# nixie.net
KiCad netlist of a schematic drawn in EAGLE
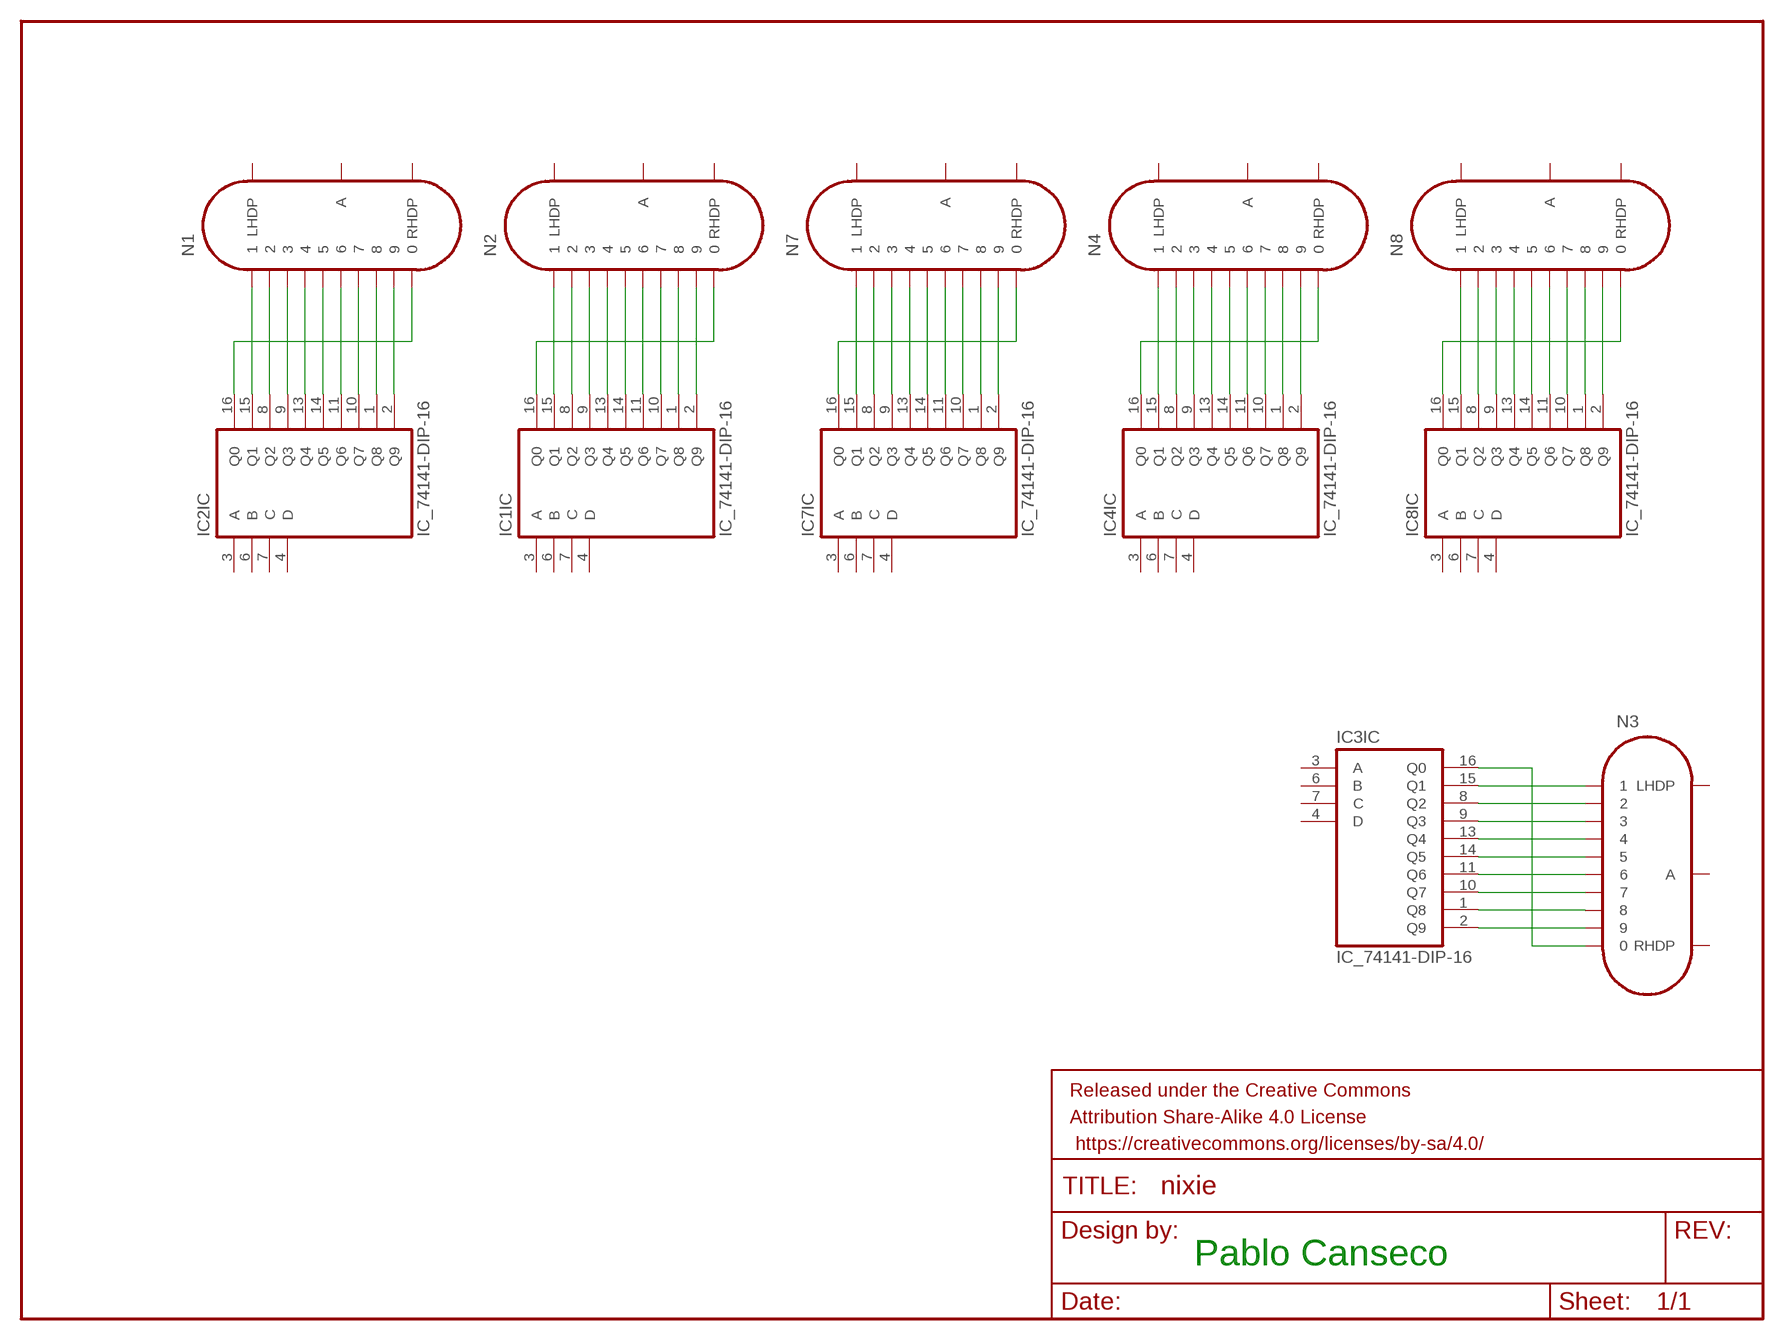
[diagram p0: schematic, sheet 1]

(export (version "E")
  (design (tool "Eeschema 10.0.6"))
  (components
    (comp (ref "FRAME1")
      (value "FRAME-LETTER")
      (footprint "eagle-import:CREATIVE_COMMONS")
      (libsource (lib "eagle-import") (part "FRAME-LETTER"))
    )
    (comp (ref "IC1")
      (value "IC_74141-DIP-16")
      (footprint "eagle-import:DIL16")
      (libsource (lib "eagle-import") (part "IC_74141-DIP-16"))
    )
    (comp (ref "IC2")
      (value "IC_74141-DIP-16")
      (footprint "eagle-import:DIL16")
      (libsource (lib "eagle-import") (part "IC_74141-DIP-16"))
    )
    (comp (ref "IC3")
      (value "IC_74141-DIP-16")
      (footprint "eagle-import:DIL16")
      (libsource (lib "eagle-import") (part "IC_74141-DIP-16"))
    )
    (comp (ref "IC4")
      (value "IC_74141-DIP-16")
      (footprint "eagle-import:DIL16")
      (libsource (lib "eagle-import") (part "IC_74141-DIP-16"))
    )
    (comp (ref "IC7")
      (value "IC_74141-DIP-16")
      (footprint "eagle-import:DIL16")
      (libsource (lib "eagle-import") (part "IC_74141-DIP-16"))
    )
    (comp (ref "IC8")
      (value "IC_74141-DIP-16")
      (footprint "eagle-import:DIL16")
      (libsource (lib "eagle-import") (part "IC_74141-DIP-16"))
    )
    (comp (ref "N1")
      (value "IN-16")
      (footprint "eagle-import:IN-16")
      (libsource (lib "eagle-import") (part "IN-16"))
    )
    (comp (ref "N2")
      (value "IN-16")
      (footprint "eagle-import:IN-16")
      (libsource (lib "eagle-import") (part "IN-16"))
    )
    (comp (ref "N3")
      (value "IN-16")
      (footprint "eagle-import:IN-16")
      (libsource (lib "eagle-import") (part "IN-16"))
    )
    (comp (ref "N4")
      (value "IN-16")
      (footprint "eagle-import:IN-16")
      (libsource (lib "eagle-import") (part "IN-16"))
    )
    (comp (ref "N7")
      (value "IN-16")
      (footprint "eagle-import:IN-16")
      (libsource (lib "eagle-import") (part "IN-16"))
    )
    (comp (ref "N8")
      (value "IN-16")
      (footprint "eagle-import:IN-16")
      (libsource (lib "eagle-import") (part "IN-16"))
    )
  )
  (nets
    (net (code "1") (name "Net-(IC1A-Q0)") (class "Default")
      (node (ref "IC1") (pin "16") (pinfunction "Q0_16") (pintype "output"))
      (node (ref "N2") (pin "0") (pinfunction "0_0") (pintype "bidirectional"))
    )
    (net (code "2") (name "Net-(IC1A-Q1)") (class "Default")
      (node (ref "IC1") (pin "15") (pinfunction "Q1_15") (pintype "output"))
      (node (ref "N2") (pin "1") (pinfunction "1_1") (pintype "bidirectional"))
    )
    (net (code "3") (name "Net-(IC1A-Q2)") (class "Default")
      (node (ref "IC1") (pin "8") (pinfunction "Q2_8") (pintype "output"))
      (node (ref "N2") (pin "2") (pinfunction "2_2") (pintype "bidirectional"))
    )
    (net (code "4") (name "Net-(IC1A-Q3)") (class "Default")
      (node (ref "IC1") (pin "9") (pinfunction "Q3_9") (pintype "output"))
      (node (ref "N2") (pin "3") (pinfunction "3_3") (pintype "bidirectional"))
    )
    (net (code "5") (name "Net-(IC1A-Q4)") (class "Default")
      (node (ref "IC1") (pin "13") (pinfunction "Q4_13") (pintype "output"))
      (node (ref "N2") (pin "4") (pinfunction "4_4") (pintype "bidirectional"))
    )
    (net (code "6") (name "Net-(IC1A-Q5)") (class "Default")
      (node (ref "IC1") (pin "14") (pinfunction "Q5_14") (pintype "output"))
      (node (ref "N2") (pin "5") (pinfunction "5_5") (pintype "bidirectional"))
    )
    (net (code "7") (name "Net-(IC1A-Q6)") (class "Default")
      (node (ref "IC1") (pin "11") (pinfunction "Q6_11") (pintype "output"))
      (node (ref "N2") (pin "6") (pinfunction "6_6") (pintype "bidirectional"))
    )
    (net (code "8") (name "Net-(IC1A-Q7)") (class "Default")
      (node (ref "IC1") (pin "10") (pinfunction "Q7_10") (pintype "output"))
      (node (ref "N2") (pin "7") (pinfunction "7_7") (pintype "bidirectional"))
    )
    (net (code "9") (name "Net-(IC1A-Q8)") (class "Default")
      (node (ref "IC1") (pin "1") (pinfunction "Q8_1") (pintype "output"))
      (node (ref "N2") (pin "8") (pinfunction "8_8") (pintype "bidirectional"))
    )
    (net (code "10") (name "Net-(IC1A-Q9)") (class "Default")
      (node (ref "IC1") (pin "2") (pinfunction "Q9_2") (pintype "output"))
      (node (ref "N2") (pin "9") (pinfunction "9_9") (pintype "bidirectional"))
    )
    (net (code "11") (name "Net-(IC2A-Q0)") (class "Default")
      (node (ref "IC2") (pin "16") (pinfunction "Q0_16") (pintype "output"))
      (node (ref "N1") (pin "0") (pinfunction "0_0") (pintype "bidirectional"))
    )
    (net (code "12") (name "Net-(IC2A-Q1)") (class "Default")
      (node (ref "IC2") (pin "15") (pinfunction "Q1_15") (pintype "output"))
      (node (ref "N1") (pin "1") (pinfunction "1_1") (pintype "bidirectional"))
    )
    (net (code "13") (name "Net-(IC2A-Q2)") (class "Default")
      (node (ref "IC2") (pin "8") (pinfunction "Q2_8") (pintype "output"))
      (node (ref "N1") (pin "2") (pinfunction "2_2") (pintype "bidirectional"))
    )
    (net (code "14") (name "Net-(IC2A-Q3)") (class "Default")
      (node (ref "IC2") (pin "9") (pinfunction "Q3_9") (pintype "output"))
      (node (ref "N1") (pin "3") (pinfunction "3_3") (pintype "bidirectional"))
    )
    (net (code "15") (name "Net-(IC2A-Q4)") (class "Default")
      (node (ref "IC2") (pin "13") (pinfunction "Q4_13") (pintype "output"))
      (node (ref "N1") (pin "4") (pinfunction "4_4") (pintype "bidirectional"))
    )
    (net (code "16") (name "Net-(IC2A-Q5)") (class "Default")
      (node (ref "IC2") (pin "14") (pinfunction "Q5_14") (pintype "output"))
      (node (ref "N1") (pin "5") (pinfunction "5_5") (pintype "bidirectional"))
    )
    (net (code "17") (name "Net-(IC2A-Q6)") (class "Default")
      (node (ref "IC2") (pin "11") (pinfunction "Q6_11") (pintype "output"))
      (node (ref "N1") (pin "6") (pinfunction "6_6") (pintype "bidirectional"))
    )
    (net (code "18") (name "Net-(IC2A-Q7)") (class "Default")
      (node (ref "IC2") (pin "10") (pinfunction "Q7_10") (pintype "output"))
      (node (ref "N1") (pin "7") (pinfunction "7_7") (pintype "bidirectional"))
    )
    (net (code "19") (name "Net-(IC2A-Q8)") (class "Default")
      (node (ref "IC2") (pin "1") (pinfunction "Q8_1") (pintype "output"))
      (node (ref "N1") (pin "8") (pinfunction "8_8") (pintype "bidirectional"))
    )
    (net (code "20") (name "Net-(IC2A-Q9)") (class "Default")
      (node (ref "IC2") (pin "2") (pinfunction "Q9_2") (pintype "output"))
      (node (ref "N1") (pin "9") (pinfunction "9_9") (pintype "bidirectional"))
    )
    (net (code "21") (name "Net-(IC3A-Q0)") (class "Default")
      (node (ref "IC3") (pin "16") (pinfunction "Q0_16") (pintype "output"))
      (node (ref "N3") (pin "0") (pinfunction "0_0") (pintype "bidirectional"))
    )
    (net (code "22") (name "Net-(IC3A-Q1)") (class "Default")
      (node (ref "IC3") (pin "15") (pinfunction "Q1_15") (pintype "output"))
      (node (ref "N3") (pin "1") (pinfunction "1_1") (pintype "bidirectional"))
    )
    (net (code "23") (name "Net-(IC3A-Q2)") (class "Default")
      (node (ref "IC3") (pin "8") (pinfunction "Q2_8") (pintype "output"))
      (node (ref "N3") (pin "2") (pinfunction "2_2") (pintype "bidirectional"))
    )
    (net (code "24") (name "Net-(IC3A-Q3)") (class "Default")
      (node (ref "IC3") (pin "9") (pinfunction "Q3_9") (pintype "output"))
      (node (ref "N3") (pin "3") (pinfunction "3_3") (pintype "bidirectional"))
    )
    (net (code "25") (name "Net-(IC3A-Q4)") (class "Default")
      (node (ref "IC3") (pin "13") (pinfunction "Q4_13") (pintype "output"))
      (node (ref "N3") (pin "4") (pinfunction "4_4") (pintype "bidirectional"))
    )
    (net (code "26") (name "Net-(IC3A-Q5)") (class "Default")
      (node (ref "IC3") (pin "14") (pinfunction "Q5_14") (pintype "output"))
      (node (ref "N3") (pin "5") (pinfunction "5_5") (pintype "bidirectional"))
    )
    (net (code "27") (name "Net-(IC3A-Q6)") (class "Default")
      (node (ref "IC3") (pin "11") (pinfunction "Q6_11") (pintype "output"))
      (node (ref "N3") (pin "6") (pinfunction "6_6") (pintype "bidirectional"))
    )
    (net (code "28") (name "Net-(IC3A-Q7)") (class "Default")
      (node (ref "IC3") (pin "10") (pinfunction "Q7_10") (pintype "output"))
      (node (ref "N3") (pin "7") (pinfunction "7_7") (pintype "bidirectional"))
    )
    (net (code "29") (name "Net-(IC3A-Q8)") (class "Default")
      (node (ref "IC3") (pin "1") (pinfunction "Q8_1") (pintype "output"))
      (node (ref "N3") (pin "8") (pinfunction "8_8") (pintype "bidirectional"))
    )
    (net (code "30") (name "Net-(IC3A-Q9)") (class "Default")
      (node (ref "IC3") (pin "2") (pinfunction "Q9_2") (pintype "output"))
      (node (ref "N3") (pin "9") (pinfunction "9_9") (pintype "bidirectional"))
    )
    (net (code "31") (name "Net-(IC4A-Q0)") (class "Default")
      (node (ref "IC4") (pin "16") (pinfunction "Q0_16") (pintype "output"))
      (node (ref "N4") (pin "0") (pinfunction "0_0") (pintype "bidirectional"))
    )
    (net (code "32") (name "Net-(IC4A-Q1)") (class "Default")
      (node (ref "IC4") (pin "15") (pinfunction "Q1_15") (pintype "output"))
      (node (ref "N4") (pin "1") (pinfunction "1_1") (pintype "bidirectional"))
    )
    (net (code "33") (name "Net-(IC4A-Q2)") (class "Default")
      (node (ref "IC4") (pin "8") (pinfunction "Q2_8") (pintype "output"))
      (node (ref "N4") (pin "2") (pinfunction "2_2") (pintype "bidirectional"))
    )
    (net (code "34") (name "Net-(IC4A-Q3)") (class "Default")
      (node (ref "IC4") (pin "9") (pinfunction "Q3_9") (pintype "output"))
      (node (ref "N4") (pin "3") (pinfunction "3_3") (pintype "bidirectional"))
    )
    (net (code "35") (name "Net-(IC4A-Q4)") (class "Default")
      (node (ref "IC4") (pin "13") (pinfunction "Q4_13") (pintype "output"))
      (node (ref "N4") (pin "4") (pinfunction "4_4") (pintype "bidirectional"))
    )
    (net (code "36") (name "Net-(IC4A-Q5)") (class "Default")
      (node (ref "IC4") (pin "14") (pinfunction "Q5_14") (pintype "output"))
      (node (ref "N4") (pin "5") (pinfunction "5_5") (pintype "bidirectional"))
    )
    (net (code "37") (name "Net-(IC4A-Q6)") (class "Default")
      (node (ref "IC4") (pin "11") (pinfunction "Q6_11") (pintype "output"))
      (node (ref "N4") (pin "6") (pinfunction "6_6") (pintype "bidirectional"))
    )
    (net (code "38") (name "Net-(IC4A-Q7)") (class "Default")
      (node (ref "IC4") (pin "10") (pinfunction "Q7_10") (pintype "output"))
      (node (ref "N4") (pin "7") (pinfunction "7_7") (pintype "bidirectional"))
    )
    (net (code "39") (name "Net-(IC4A-Q8)") (class "Default")
      (node (ref "IC4") (pin "1") (pinfunction "Q8_1") (pintype "output"))
      (node (ref "N4") (pin "8") (pinfunction "8_8") (pintype "bidirectional"))
    )
    (net (code "40") (name "Net-(IC4A-Q9)") (class "Default")
      (node (ref "IC4") (pin "2") (pinfunction "Q9_2") (pintype "output"))
      (node (ref "N4") (pin "9") (pinfunction "9_9") (pintype "bidirectional"))
    )
    (net (code "41") (name "Net-(IC7A-Q0)") (class "Default")
      (node (ref "IC7") (pin "16") (pinfunction "Q0_16") (pintype "output"))
      (node (ref "N7") (pin "0") (pinfunction "0_0") (pintype "bidirectional"))
    )
    (net (code "42") (name "Net-(IC7A-Q1)") (class "Default")
      (node (ref "IC7") (pin "15") (pinfunction "Q1_15") (pintype "output"))
      (node (ref "N7") (pin "1") (pinfunction "1_1") (pintype "bidirectional"))
    )
    (net (code "43") (name "Net-(IC7A-Q2)") (class "Default")
      (node (ref "IC7") (pin "8") (pinfunction "Q2_8") (pintype "output"))
      (node (ref "N7") (pin "2") (pinfunction "2_2") (pintype "bidirectional"))
    )
    (net (code "44") (name "Net-(IC7A-Q3)") (class "Default")
      (node (ref "IC7") (pin "9") (pinfunction "Q3_9") (pintype "output"))
      (node (ref "N7") (pin "3") (pinfunction "3_3") (pintype "bidirectional"))
    )
    (net (code "45") (name "Net-(IC7A-Q4)") (class "Default")
      (node (ref "IC7") (pin "13") (pinfunction "Q4_13") (pintype "output"))
      (node (ref "N7") (pin "4") (pinfunction "4_4") (pintype "bidirectional"))
    )
    (net (code "46") (name "Net-(IC7A-Q5)") (class "Default")
      (node (ref "IC7") (pin "14") (pinfunction "Q5_14") (pintype "output"))
      (node (ref "N7") (pin "5") (pinfunction "5_5") (pintype "bidirectional"))
    )
    (net (code "47") (name "Net-(IC7A-Q6)") (class "Default")
      (node (ref "IC7") (pin "11") (pinfunction "Q6_11") (pintype "output"))
      (node (ref "N7") (pin "6") (pinfunction "6_6") (pintype "bidirectional"))
    )
    (net (code "48") (name "Net-(IC7A-Q7)") (class "Default")
      (node (ref "IC7") (pin "10") (pinfunction "Q7_10") (pintype "output"))
      (node (ref "N7") (pin "7") (pinfunction "7_7") (pintype "bidirectional"))
    )
    (net (code "49") (name "Net-(IC7A-Q8)") (class "Default")
      (node (ref "IC7") (pin "1") (pinfunction "Q8_1") (pintype "output"))
      (node (ref "N7") (pin "8") (pinfunction "8_8") (pintype "bidirectional"))
    )
    (net (code "50") (name "Net-(IC7A-Q9)") (class "Default")
      (node (ref "IC7") (pin "2") (pinfunction "Q9_2") (pintype "output"))
      (node (ref "N7") (pin "9") (pinfunction "9_9") (pintype "bidirectional"))
    )
    (net (code "51") (name "Net-(IC8A-Q0)") (class "Default")
      (node (ref "IC8") (pin "16") (pinfunction "Q0_16") (pintype "output"))
      (node (ref "N8") (pin "0") (pinfunction "0_0") (pintype "bidirectional"))
    )
    (net (code "52") (name "Net-(IC8A-Q1)") (class "Default")
      (node (ref "IC8") (pin "15") (pinfunction "Q1_15") (pintype "output"))
      (node (ref "N8") (pin "1") (pinfunction "1_1") (pintype "bidirectional"))
    )
    (net (code "53") (name "Net-(IC8A-Q2)") (class "Default")
      (node (ref "IC8") (pin "8") (pinfunction "Q2_8") (pintype "output"))
      (node (ref "N8") (pin "2") (pinfunction "2_2") (pintype "bidirectional"))
    )
    (net (code "54") (name "Net-(IC8A-Q3)") (class "Default")
      (node (ref "IC8") (pin "9") (pinfunction "Q3_9") (pintype "output"))
      (node (ref "N8") (pin "3") (pinfunction "3_3") (pintype "bidirectional"))
    )
    (net (code "55") (name "Net-(IC8A-Q4)") (class "Default")
      (node (ref "IC8") (pin "13") (pinfunction "Q4_13") (pintype "output"))
      (node (ref "N8") (pin "4") (pinfunction "4_4") (pintype "bidirectional"))
    )
    (net (code "56") (name "Net-(IC8A-Q5)") (class "Default")
      (node (ref "IC8") (pin "14") (pinfunction "Q5_14") (pintype "output"))
      (node (ref "N8") (pin "5") (pinfunction "5_5") (pintype "bidirectional"))
    )
    (net (code "57") (name "Net-(IC8A-Q6)") (class "Default")
      (node (ref "IC8") (pin "11") (pinfunction "Q6_11") (pintype "output"))
      (node (ref "N8") (pin "6") (pinfunction "6_6") (pintype "bidirectional"))
    )
    (net (code "58") (name "Net-(IC8A-Q7)") (class "Default")
      (node (ref "IC8") (pin "10") (pinfunction "Q7_10") (pintype "output"))
      (node (ref "N8") (pin "7") (pinfunction "7_7") (pintype "bidirectional"))
    )
    (net (code "59") (name "Net-(IC8A-Q8)") (class "Default")
      (node (ref "IC8") (pin "1") (pinfunction "Q8_1") (pintype "output"))
      (node (ref "N8") (pin "8") (pinfunction "8_8") (pintype "bidirectional"))
    )
    (net (code "60") (name "Net-(IC8A-Q9)") (class "Default")
      (node (ref "IC8") (pin "2") (pinfunction "Q9_2") (pintype "output"))
      (node (ref "N8") (pin "9") (pinfunction "9_9") (pintype "bidirectional"))
    )
    (net (code "61") (name "unconnected-(IC1A-A-Pad3)") (class "Default")
      (node (ref "IC1") (pin "3") (pinfunction "A_3") (pintype "input"))
    )
    (net (code "62") (name "unconnected-(IC1A-B-Pad6)") (class "Default")
      (node (ref "IC1") (pin "6") (pinfunction "B_6") (pintype "input"))
    )
    (net (code "63") (name "unconnected-(IC1A-C-Pad7)") (class "Default")
      (node (ref "IC1") (pin "7") (pinfunction "C_7") (pintype "input"))
    )
    (net (code "64") (name "unconnected-(IC1A-D-Pad4)") (class "Default")
      (node (ref "IC1") (pin "4") (pinfunction "D_4") (pintype "input"))
    )
    (net (code "65") (name "unconnected-(IC2A-A-Pad3)") (class "Default")
      (node (ref "IC2") (pin "3") (pinfunction "A_3") (pintype "input"))
    )
    (net (code "66") (name "unconnected-(IC2A-B-Pad6)") (class "Default")
      (node (ref "IC2") (pin "6") (pinfunction "B_6") (pintype "input"))
    )
    (net (code "67") (name "unconnected-(IC2A-C-Pad7)") (class "Default")
      (node (ref "IC2") (pin "7") (pinfunction "C_7") (pintype "input"))
    )
    (net (code "68") (name "unconnected-(IC2A-D-Pad4)") (class "Default")
      (node (ref "IC2") (pin "4") (pinfunction "D_4") (pintype "input"))
    )
    (net (code "69") (name "unconnected-(IC3A-A-Pad3)") (class "Default")
      (node (ref "IC3") (pin "3") (pinfunction "A_3") (pintype "input"))
    )
    (net (code "70") (name "unconnected-(IC3A-B-Pad6)") (class "Default")
      (node (ref "IC3") (pin "6") (pinfunction "B_6") (pintype "input"))
    )
    (net (code "71") (name "unconnected-(IC3A-C-Pad7)") (class "Default")
      (node (ref "IC3") (pin "7") (pinfunction "C_7") (pintype "input"))
    )
    (net (code "72") (name "unconnected-(IC3A-D-Pad4)") (class "Default")
      (node (ref "IC3") (pin "4") (pinfunction "D_4") (pintype "input"))
    )
    (net (code "73") (name "unconnected-(IC4A-A-Pad3)") (class "Default")
      (node (ref "IC4") (pin "3") (pinfunction "A_3") (pintype "input"))
    )
    (net (code "74") (name "unconnected-(IC4A-B-Pad6)") (class "Default")
      (node (ref "IC4") (pin "6") (pinfunction "B_6") (pintype "input"))
    )
    (net (code "75") (name "unconnected-(IC4A-C-Pad7)") (class "Default")
      (node (ref "IC4") (pin "7") (pinfunction "C_7") (pintype "input"))
    )
    (net (code "76") (name "unconnected-(IC4A-D-Pad4)") (class "Default")
      (node (ref "IC4") (pin "4") (pinfunction "D_4") (pintype "input"))
    )
    (net (code "77") (name "unconnected-(IC7A-A-Pad3)") (class "Default")
      (node (ref "IC7") (pin "3") (pinfunction "A_3") (pintype "input"))
    )
    (net (code "78") (name "unconnected-(IC7A-B-Pad6)") (class "Default")
      (node (ref "IC7") (pin "6") (pinfunction "B_6") (pintype "input"))
    )
    (net (code "79") (name "unconnected-(IC7A-C-Pad7)") (class "Default")
      (node (ref "IC7") (pin "7") (pinfunction "C_7") (pintype "input"))
    )
    (net (code "80") (name "unconnected-(IC7A-D-Pad4)") (class "Default")
      (node (ref "IC7") (pin "4") (pinfunction "D_4") (pintype "input"))
    )
    (net (code "81") (name "unconnected-(IC8A-A-Pad3)") (class "Default")
      (node (ref "IC8") (pin "3") (pinfunction "A_3") (pintype "input"))
    )
    (net (code "82") (name "unconnected-(IC8A-B-Pad6)") (class "Default")
      (node (ref "IC8") (pin "6") (pinfunction "B_6") (pintype "input"))
    )
    (net (code "83") (name "unconnected-(IC8A-C-Pad7)") (class "Default")
      (node (ref "IC8") (pin "7") (pinfunction "C_7") (pintype "input"))
    )
    (net (code "84") (name "unconnected-(IC8A-D-Pad4)") (class "Default")
      (node (ref "IC8") (pin "4") (pinfunction "D_4") (pintype "input"))
    )
    (net (code "85") (name "unconnected-(N1-PadA)") (class "Default")
      (node (ref "N1") (pin "A") (pinfunction "A_A") (pintype "bidirectional"))
    )
    (net (code "86") (name "unconnected-(N1-PadLHDP)") (class "Default")
      (node (ref "N1") (pin "LHDP") (pinfunction "LHDP_LHDP") (pintype "bidirectional"))
    )
    (net (code "87") (name "unconnected-(N1-PadRHDP)") (class "Default")
      (node (ref "N1") (pin "RHDP") (pinfunction "RHDP_RHDP") (pintype "bidirectional"))
    )
    (net (code "88") (name "unconnected-(N2-PadA)") (class "Default")
      (node (ref "N2") (pin "A") (pinfunction "A_A") (pintype "bidirectional"))
    )
    (net (code "89") (name "unconnected-(N2-PadLHDP)") (class "Default")
      (node (ref "N2") (pin "LHDP") (pinfunction "LHDP_LHDP") (pintype "bidirectional"))
    )
    (net (code "90") (name "unconnected-(N2-PadRHDP)") (class "Default")
      (node (ref "N2") (pin "RHDP") (pinfunction "RHDP_RHDP") (pintype "bidirectional"))
    )
    (net (code "91") (name "unconnected-(N3-PadA)") (class "Default")
      (node (ref "N3") (pin "A") (pinfunction "A_A") (pintype "bidirectional"))
    )
    (net (code "92") (name "unconnected-(N3-PadLHDP)") (class "Default")
      (node (ref "N3") (pin "LHDP") (pinfunction "LHDP_LHDP") (pintype "bidirectional"))
    )
    (net (code "93") (name "unconnected-(N3-PadRHDP)") (class "Default")
      (node (ref "N3") (pin "RHDP") (pinfunction "RHDP_RHDP") (pintype "bidirectional"))
    )
    (net (code "94") (name "unconnected-(N4-PadA)") (class "Default")
      (node (ref "N4") (pin "A") (pinfunction "A_A") (pintype "bidirectional"))
    )
    (net (code "95") (name "unconnected-(N4-PadLHDP)") (class "Default")
      (node (ref "N4") (pin "LHDP") (pinfunction "LHDP_LHDP") (pintype "bidirectional"))
    )
    (net (code "96") (name "unconnected-(N4-PadRHDP)") (class "Default")
      (node (ref "N4") (pin "RHDP") (pinfunction "RHDP_RHDP") (pintype "bidirectional"))
    )
    (net (code "97") (name "unconnected-(N7-PadA)") (class "Default")
      (node (ref "N7") (pin "A") (pinfunction "A_A") (pintype "bidirectional"))
    )
    (net (code "98") (name "unconnected-(N7-PadLHDP)") (class "Default")
      (node (ref "N7") (pin "LHDP") (pinfunction "LHDP_LHDP") (pintype "bidirectional"))
    )
    (net (code "99") (name "unconnected-(N7-PadRHDP)") (class "Default")
      (node (ref "N7") (pin "RHDP") (pinfunction "RHDP_RHDP") (pintype "bidirectional"))
    )
    (net (code "100") (name "unconnected-(N8-PadA)") (class "Default")
      (node (ref "N8") (pin "A") (pinfunction "A_A") (pintype "bidirectional"))
    )
    (net (code "101") (name "unconnected-(N8-PadLHDP)") (class "Default")
      (node (ref "N8") (pin "LHDP") (pinfunction "LHDP_LHDP") (pintype "bidirectional"))
    )
    (net (code "102") (name "unconnected-(N8-PadRHDP)") (class "Default")
      (node (ref "N8") (pin "RHDP") (pinfunction "RHDP_RHDP") (pintype "bidirectional"))
    )
  )
)
